# hover_controller1.net
KiCad netlist of a schematic drawn in EAGLE
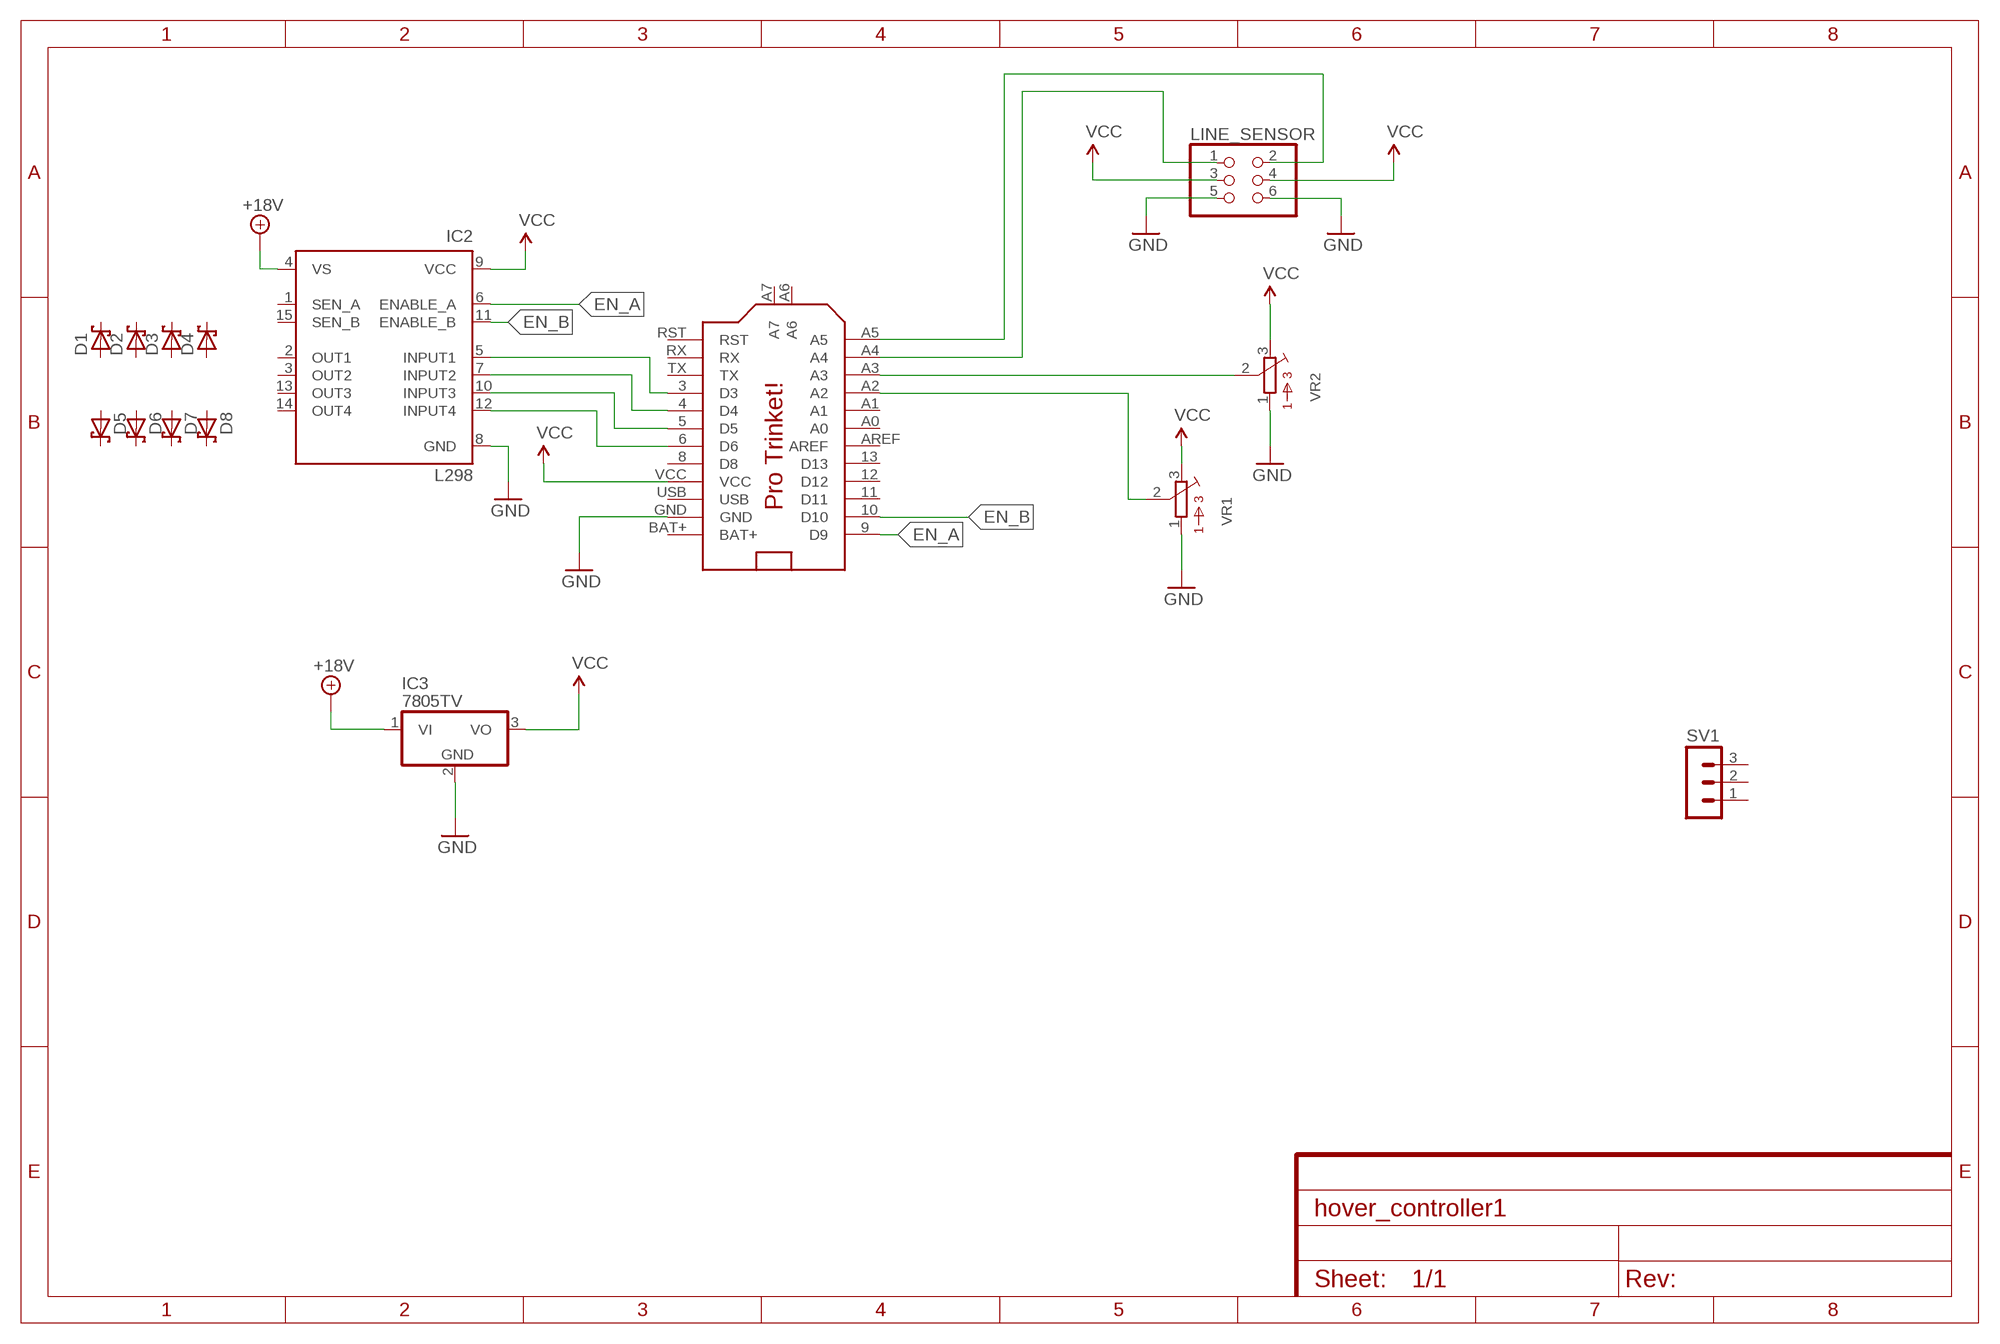
[diagram p0: schematic, sheet 1]

(export (version "E")
  (design (tool "Eeschema 10.0.6"))
  (components
    (comp (ref "D1")
      (value "SCHOTTKY-DIODEDO35-7")
      (footprint "eagle-import:DO35-7")
      (libsource (lib "eagle-import") (part "SCHOTTKY-DIODEDO35-7"))
    )
    (comp (ref "D2")
      (value "SCHOTTKY-DIODEDO35-7")
      (footprint "eagle-import:DO35-7")
      (libsource (lib "eagle-import") (part "SCHOTTKY-DIODEDO35-7"))
    )
    (comp (ref "D3")
      (value "SCHOTTKY-DIODEDO35-7")
      (footprint "eagle-import:DO35-7")
      (libsource (lib "eagle-import") (part "SCHOTTKY-DIODEDO35-7"))
    )
    (comp (ref "D4")
      (value "SCHOTTKY-DIODEDO35-7")
      (footprint "eagle-import:DO35-7")
      (libsource (lib "eagle-import") (part "SCHOTTKY-DIODEDO35-7"))
    )
    (comp (ref "D5")
      (value "SCHOTTKY-DIODEDO35-7")
      (footprint "eagle-import:DO35-7")
      (libsource (lib "eagle-import") (part "SCHOTTKY-DIODEDO35-7"))
    )
    (comp (ref "D6")
      (value "SCHOTTKY-DIODEDO35-7")
      (footprint "eagle-import:DO35-7")
      (libsource (lib "eagle-import") (part "SCHOTTKY-DIODEDO35-7"))
    )
    (comp (ref "D7")
      (value "SCHOTTKY-DIODEDO35-7")
      (footprint "eagle-import:DO35-7")
      (libsource (lib "eagle-import") (part "SCHOTTKY-DIODEDO35-7"))
    )
    (comp (ref "D8")
      (value "SCHOTTKY-DIODEDO35-7")
      (footprint "eagle-import:DO35-7")
      (libsource (lib "eagle-import") (part "SCHOTTKY-DIODEDO35-7"))
    )
    (comp (ref "IC2")
      (value "L298")
      (footprint "eagle-import:MULTIWATT-15")
      (fields (field (name "MPN") "L298N"))
      (libsource (lib "eagle-import") (part "L298"))
    )
    (comp (ref "IC3")
      (value "7805TV")
      (footprint "eagle-import:TO220V")
      (libsource (lib "eagle-import") (part "78TV05"))
    )
    (comp (ref "LINE_SENSOR")
      (value "PINHD-2X3")
      (footprint "eagle-import:2X03")
      (libsource (lib "eagle-import") (part "PINHD-2X3"))
    )
    (comp (ref "SV1")
      (value "MA03-1")
      (footprint "eagle-import:MA03-1")
      (libsource (lib "eagle-import") (part "MA03-1"))
    )
    (comp (ref "U$1")
      (value "PRO_TRINKET")
      (footprint "eagle-import:PROTRINKET")
      (libsource (lib "eagle-import") (part "PRO_TRINKET"))
    )
    (comp (ref "VR1")
      (value "BOURNS_3362P_TRIMMERP")
      (footprint "eagle-import:BOURNS_3362P_TRIMMER")
      (libsource (lib "eagle-import") (part "BOURNS_3362P_TRIMMERP"))
    )
    (comp (ref "VR2")
      (value "BOURNS_3362P_TRIMMERP")
      (footprint "eagle-import:BOURNS_3362P_TRIMMER")
      (libsource (lib "eagle-import") (part "BOURNS_3362P_TRIMMERP"))
    )
  )
  (nets
    (net (code "1") (name "+18V") (class "Default")
      (node (ref "IC2") (pin "4") (pinfunction "VS_4") (pintype "power_in"))
      (node (ref "IC3") (pin "1") (pinfunction "VI_1") (pintype "input"))
    )
    (net (code "2") (name "/BAT+") (class "Default")
      (node (ref "U$1") (pin "BAT+") (pinfunction "BAT+_BAT+") (pintype "power_in"))
    )
    (net (code "3") (name "/USB") (class "Default")
      (node (ref "U$1") (pin "USB") (pinfunction "USB_USB") (pintype "power_in"))
    )
    (net (code "4") (name "EN_A") (class "Default")
      (node (ref "IC2") (pin "6") (pinfunction "ENABLE_A_6") (pintype "input"))
      (node (ref "U$1") (pin "9") (pinfunction "D9_9") (pintype "bidirectional"))
    )
    (net (code "5") (name "EN_B") (class "Default")
      (node (ref "IC2") (pin "11") (pinfunction "ENABLE_B_11") (pintype "input"))
      (node (ref "U$1") (pin "10") (pinfunction "D10_10") (pintype "bidirectional"))
    )
    (net (code "6") (name "GND") (class "Default")
      (node (ref "IC2") (pin "8") (pinfunction "GND_8") (pintype "power_in"))
      (node (ref "IC3") (pin "2") (pinfunction "GND_2") (pintype "passive"))
      (node (ref "LINE_SENSOR") (pin "5") (pinfunction "5_5") (pintype "passive"))
      (node (ref "LINE_SENSOR") (pin "6") (pinfunction "6_6") (pintype "passive"))
      (node (ref "U$1") (pin "GND") (pinfunction "GND_GND") (pintype "power_in"))
      (node (ref "VR1") (pin "1") (pinfunction "1_1") (pintype "passive"))
      (node (ref "VR2") (pin "1") (pinfunction "1_1") (pintype "passive"))
    )
    (net (code "7") (name "Net-(IC2-INPUT1)") (class "Default")
      (node (ref "IC2") (pin "5") (pinfunction "INPUT1_5") (pintype "input"))
      (node (ref "U$1") (pin "3") (pinfunction "D3_3") (pintype "bidirectional"))
    )
    (net (code "8") (name "Net-(IC2-INPUT2)") (class "Default")
      (node (ref "IC2") (pin "7") (pinfunction "INPUT2_7") (pintype "input"))
      (node (ref "U$1") (pin "4") (pinfunction "D4_4") (pintype "bidirectional"))
    )
    (net (code "9") (name "Net-(IC2-INPUT3)") (class "Default")
      (node (ref "IC2") (pin "10") (pinfunction "INPUT3_10") (pintype "input"))
      (node (ref "U$1") (pin "5") (pinfunction "D5_5") (pintype "bidirectional"))
    )
    (net (code "10") (name "Net-(IC2-INPUT4)") (class "Default")
      (node (ref "IC2") (pin "12") (pinfunction "INPUT4_12") (pintype "input"))
      (node (ref "U$1") (pin "6") (pinfunction "D6_6") (pintype "bidirectional"))
    )
    (net (code "11") (name "Net-(LINE_SENSOR-Pad1)") (class "Default")
      (node (ref "LINE_SENSOR") (pin "1") (pinfunction "1_1") (pintype "passive"))
      (node (ref "U$1") (pin "A4") (pinfunction "A4_A4") (pintype "bidirectional"))
    )
    (net (code "12") (name "Net-(LINE_SENSOR-Pad2)") (class "Default")
      (node (ref "LINE_SENSOR") (pin "2") (pinfunction "2_2") (pintype "passive"))
      (node (ref "U$1") (pin "A5") (pinfunction "A5_A5") (pintype "bidirectional"))
    )
    (net (code "13") (name "Net-(U$1-PadA2)") (class "Default")
      (node (ref "U$1") (pin "A2") (pinfunction "A2_A2") (pintype "bidirectional"))
      (node (ref "VR1") (pin "2") (pinfunction "2_2") (pintype "passive"))
    )
    (net (code "14") (name "Net-(U$1-PadA3)") (class "Default")
      (node (ref "U$1") (pin "A3") (pinfunction "A3_A3") (pintype "bidirectional"))
      (node (ref "VR2") (pin "2") (pinfunction "2_2") (pintype "passive"))
    )
    (net (code "15") (name "VCC") (class "Default")
      (node (ref "IC2") (pin "9") (pinfunction "VCC_9") (pintype "power_in"))
      (node (ref "IC3") (pin "3") (pinfunction "VO_3") (pintype "passive"))
      (node (ref "LINE_SENSOR") (pin "3") (pinfunction "3_3") (pintype "passive"))
      (node (ref "LINE_SENSOR") (pin "4") (pinfunction "4_4") (pintype "passive"))
      (node (ref "U$1") (pin "VCC") (pinfunction "VCC_VCC") (pintype "power_in"))
      (node (ref "VR1") (pin "3") (pinfunction "3_3") (pintype "passive"))
      (node (ref "VR2") (pin "3") (pinfunction "3_3") (pintype "passive"))
    )
    (net (code "16") (name "unconnected-(D1-PadA)") (class "Default")
      (node (ref "D1") (pin "A") (pinfunction "A_A") (pintype "passive"))
    )
    (net (code "17") (name "unconnected-(D1-PadC)") (class "Default")
      (node (ref "D1") (pin "C") (pinfunction "C_C") (pintype "passive"))
    )
    (net (code "18") (name "unconnected-(D2-PadA)") (class "Default")
      (node (ref "D2") (pin "A") (pinfunction "A_A") (pintype "passive"))
    )
    (net (code "19") (name "unconnected-(D2-PadC)") (class "Default")
      (node (ref "D2") (pin "C") (pinfunction "C_C") (pintype "passive"))
    )
    (net (code "20") (name "unconnected-(D3-PadA)") (class "Default")
      (node (ref "D3") (pin "A") (pinfunction "A_A") (pintype "passive"))
    )
    (net (code "21") (name "unconnected-(D3-PadC)") (class "Default")
      (node (ref "D3") (pin "C") (pinfunction "C_C") (pintype "passive"))
    )
    (net (code "22") (name "unconnected-(D4-PadA)") (class "Default")
      (node (ref "D4") (pin "A") (pinfunction "A_A") (pintype "passive"))
    )
    (net (code "23") (name "unconnected-(D4-PadC)") (class "Default")
      (node (ref "D4") (pin "C") (pinfunction "C_C") (pintype "passive"))
    )
    (net (code "24") (name "unconnected-(D5-PadA)") (class "Default")
      (node (ref "D5") (pin "A") (pinfunction "A_A") (pintype "passive"))
    )
    (net (code "25") (name "unconnected-(D5-PadC)") (class "Default")
      (node (ref "D5") (pin "C") (pinfunction "C_C") (pintype "passive"))
    )
    (net (code "26") (name "unconnected-(D6-PadA)") (class "Default")
      (node (ref "D6") (pin "A") (pinfunction "A_A") (pintype "passive"))
    )
    (net (code "27") (name "unconnected-(D6-PadC)") (class "Default")
      (node (ref "D6") (pin "C") (pinfunction "C_C") (pintype "passive"))
    )
    (net (code "28") (name "unconnected-(D7-PadA)") (class "Default")
      (node (ref "D7") (pin "A") (pinfunction "A_A") (pintype "passive"))
    )
    (net (code "29") (name "unconnected-(D7-PadC)") (class "Default")
      (node (ref "D7") (pin "C") (pinfunction "C_C") (pintype "passive"))
    )
    (net (code "30") (name "unconnected-(D8-PadA)") (class "Default")
      (node (ref "D8") (pin "A") (pinfunction "A_A") (pintype "passive"))
    )
    (net (code "31") (name "unconnected-(D8-PadC)") (class "Default")
      (node (ref "D8") (pin "C") (pinfunction "C_C") (pintype "passive"))
    )
    (net (code "32") (name "unconnected-(IC2-OUT1-Pad2)") (class "Default")
      (node (ref "IC2") (pin "2") (pinfunction "OUT1_2") (pintype "output"))
    )
    (net (code "33") (name "unconnected-(IC2-OUT2-Pad3)") (class "Default")
      (node (ref "IC2") (pin "3") (pinfunction "OUT2_3") (pintype "output"))
    )
    (net (code "34") (name "unconnected-(IC2-OUT3-Pad13)") (class "Default")
      (node (ref "IC2") (pin "13") (pinfunction "OUT3_13") (pintype "output"))
    )
    (net (code "35") (name "unconnected-(IC2-OUT4-Pad14)") (class "Default")
      (node (ref "IC2") (pin "14") (pinfunction "OUT4_14") (pintype "output"))
    )
    (net (code "36") (name "unconnected-(IC2-SEN_A-Pad1)") (class "Default")
      (node (ref "IC2") (pin "1") (pinfunction "SEN_A_1") (pintype "input"))
    )
    (net (code "37") (name "unconnected-(IC2-SEN_B-Pad15)") (class "Default")
      (node (ref "IC2") (pin "15") (pinfunction "SEN_B_15") (pintype "input"))
    )
    (net (code "38") (name "unconnected-(SV1-Pad1)") (class "Default")
      (node (ref "SV1") (pin "1") (pinfunction "1_1") (pintype "passive"))
    )
    (net (code "39") (name "unconnected-(SV1-Pad2)") (class "Default")
      (node (ref "SV1") (pin "2") (pinfunction "2_2") (pintype "passive"))
    )
    (net (code "40") (name "unconnected-(SV1-Pad3)") (class "Default")
      (node (ref "SV1") (pin "3") (pinfunction "3_3") (pintype "passive"))
    )
    (net (code "41") (name "unconnected-(U$1-D8-Pad8)") (class "Default")
      (node (ref "U$1") (pin "8") (pinfunction "D8_8") (pintype "bidirectional"))
    )
    (net (code "42") (name "unconnected-(U$1-D11-Pad11)") (class "Default")
      (node (ref "U$1") (pin "11") (pinfunction "D11_11") (pintype "bidirectional"))
    )
    (net (code "43") (name "unconnected-(U$1-D12-Pad12)") (class "Default")
      (node (ref "U$1") (pin "12") (pinfunction "D12_12") (pintype "bidirectional"))
    )
    (net (code "44") (name "unconnected-(U$1-D13-Pad13)") (class "Default")
      (node (ref "U$1") (pin "13") (pinfunction "D13_13") (pintype "bidirectional"))
    )
    (net (code "45") (name "unconnected-(U$1-PadA0)") (class "Default")
      (node (ref "U$1") (pin "A0") (pinfunction "A0_A0") (pintype "bidirectional"))
    )
    (net (code "46") (name "unconnected-(U$1-PadA1)") (class "Default")
      (node (ref "U$1") (pin "A1") (pinfunction "A1_A1") (pintype "bidirectional"))
    )
    (net (code "47") (name "unconnected-(U$1-PadA6)") (class "Default")
      (node (ref "U$1") (pin "A6") (pinfunction "A6_A6") (pintype "passive"))
    )
    (net (code "48") (name "unconnected-(U$1-PadA7)") (class "Default")
      (node (ref "U$1") (pin "A7") (pinfunction "A7_A7") (pintype "passive"))
    )
    (net (code "49") (name "unconnected-(U$1-PadAREF)") (class "Default")
      (node (ref "U$1") (pin "AREF") (pinfunction "AREF_AREF") (pintype "passive"))
    )
    (net (code "50") (name "unconnected-(U$1-PadRST)") (class "Default")
      (node (ref "U$1") (pin "RST") (pinfunction "RST_RST") (pintype "passive"))
    )
    (net (code "51") (name "unconnected-(U$1-PadRX)") (class "Default")
      (node (ref "U$1") (pin "RX") (pinfunction "RX_RX") (pintype "bidirectional"))
    )
    (net (code "52") (name "unconnected-(U$1-PadTX)") (class "Default")
      (node (ref "U$1") (pin "TX") (pinfunction "TX_TX") (pintype "bidirectional"))
    )
  )
)
